# M_F_ext_breadboard.net
KiCad netlist of a schematic drawn in EAGLE
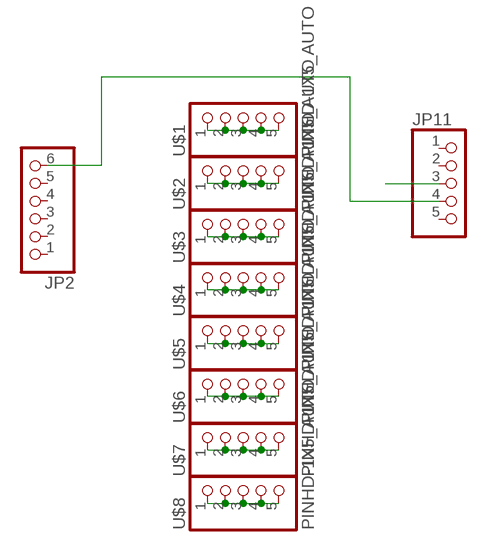
[diagram p0: schematic, sheet 1]

(export (version "E")
  (design (tool "Eeschema 10.0.6"))
  (components
    (comp (ref "JP2")
      (value "PINHD-1X6")
      (footprint "eagle-import:1X06")
      (libsource (lib "eagle-import") (part "PINHD-1X6"))
    )
    (comp (ref "JP11")
      (value "PINHD-1X5")
      (footprint "eagle-import:1X05")
      (libsource (lib "eagle-import") (part "PINHD-1X5"))
    )
    (comp (ref "U$1")
      (value "PINHD-1X5_AUTO")
      (footprint "eagle-import:1X5_AUTO")
      (libsource (lib "eagle-import") (part "PINHD-1X5_AUTO"))
    )
    (comp (ref "U$2")
      (value "PINHD-1X5_AUTO")
      (footprint "eagle-import:1X5_AUTO")
      (libsource (lib "eagle-import") (part "PINHD-1X5_AUTO"))
    )
    (comp (ref "U$3")
      (value "PINHD-1X5_AUTO")
      (footprint "eagle-import:1X5_AUTO")
      (libsource (lib "eagle-import") (part "PINHD-1X5_AUTO"))
    )
    (comp (ref "U$4")
      (value "PINHD-1X5_AUTO")
      (footprint "eagle-import:1X5_AUTO")
      (libsource (lib "eagle-import") (part "PINHD-1X5_AUTO"))
    )
    (comp (ref "U$5")
      (value "PINHD-1X5_AUTO")
      (footprint "eagle-import:1X5_AUTO")
      (libsource (lib "eagle-import") (part "PINHD-1X5_AUTO"))
    )
    (comp (ref "U$6")
      (value "PINHD-1X5_AUTO")
      (footprint "eagle-import:1X5_AUTO")
      (libsource (lib "eagle-import") (part "PINHD-1X5_AUTO"))
    )
    (comp (ref "U$7")
      (value "PINHD-1X5_AUTO")
      (footprint "eagle-import:1X5_AUTO")
      (libsource (lib "eagle-import") (part "PINHD-1X5_AUTO"))
    )
    (comp (ref "U$8")
      (value "PINHD-1X5_AUTO")
      (footprint "eagle-import:1X5_AUTO")
      (libsource (lib "eagle-import") (part "PINHD-1X5_AUTO"))
    )
  )
  (nets
    (net (code "1") (name "Net-(JP11-Pad4)") (class "Default")
      (node (ref "JP11") (pin "4") (pinfunction "4_4") (pintype "passive"))
      (node (ref "JP2") (pin "6") (pinfunction "6_6") (pintype "passive"))
    )
    (net (code "2") (name "Net-(U$1-Pad1)") (class "Default")
      (node (ref "U$1") (pin "1") (pinfunction "1_1") (pintype "passive"))
      (node (ref "U$1") (pin "2") (pinfunction "2_2") (pintype "passive"))
      (node (ref "U$1") (pin "3") (pinfunction "3_3") (pintype "passive"))
      (node (ref "U$1") (pin "4") (pinfunction "4_4") (pintype "passive"))
      (node (ref "U$1") (pin "5") (pinfunction "5_5") (pintype "passive"))
    )
    (net (code "3") (name "Net-(U$2-Pad1)") (class "Default")
      (node (ref "U$2") (pin "1") (pinfunction "1_1") (pintype "passive"))
      (node (ref "U$2") (pin "2") (pinfunction "2_2") (pintype "passive"))
      (node (ref "U$2") (pin "3") (pinfunction "3_3") (pintype "passive"))
      (node (ref "U$2") (pin "4") (pinfunction "4_4") (pintype "passive"))
      (node (ref "U$2") (pin "5") (pinfunction "5_5") (pintype "passive"))
    )
    (net (code "4") (name "Net-(U$3-Pad1)") (class "Default")
      (node (ref "U$3") (pin "1") (pinfunction "1_1") (pintype "passive"))
      (node (ref "U$3") (pin "2") (pinfunction "2_2") (pintype "passive"))
      (node (ref "U$3") (pin "3") (pinfunction "3_3") (pintype "passive"))
      (node (ref "U$3") (pin "4") (pinfunction "4_4") (pintype "passive"))
      (node (ref "U$3") (pin "5") (pinfunction "5_5") (pintype "passive"))
    )
    (net (code "5") (name "Net-(U$4-Pad1)") (class "Default")
      (node (ref "U$4") (pin "1") (pinfunction "1_1") (pintype "passive"))
      (node (ref "U$4") (pin "2") (pinfunction "2_2") (pintype "passive"))
      (node (ref "U$4") (pin "3") (pinfunction "3_3") (pintype "passive"))
      (node (ref "U$4") (pin "4") (pinfunction "4_4") (pintype "passive"))
      (node (ref "U$4") (pin "5") (pinfunction "5_5") (pintype "passive"))
    )
    (net (code "6") (name "Net-(U$5-Pad1)") (class "Default")
      (node (ref "U$5") (pin "1") (pinfunction "1_1") (pintype "passive"))
      (node (ref "U$5") (pin "2") (pinfunction "2_2") (pintype "passive"))
      (node (ref "U$5") (pin "3") (pinfunction "3_3") (pintype "passive"))
      (node (ref "U$5") (pin "4") (pinfunction "4_4") (pintype "passive"))
      (node (ref "U$5") (pin "5") (pinfunction "5_5") (pintype "passive"))
    )
    (net (code "7") (name "Net-(U$6-Pad1)") (class "Default")
      (node (ref "U$6") (pin "1") (pinfunction "1_1") (pintype "passive"))
      (node (ref "U$6") (pin "2") (pinfunction "2_2") (pintype "passive"))
      (node (ref "U$6") (pin "3") (pinfunction "3_3") (pintype "passive"))
      (node (ref "U$6") (pin "4") (pinfunction "4_4") (pintype "passive"))
      (node (ref "U$6") (pin "5") (pinfunction "5_5") (pintype "passive"))
    )
    (net (code "8") (name "Net-(U$7-Pad1)") (class "Default")
      (node (ref "U$7") (pin "1") (pinfunction "1_1") (pintype "passive"))
      (node (ref "U$7") (pin "2") (pinfunction "2_2") (pintype "passive"))
      (node (ref "U$7") (pin "3") (pinfunction "3_3") (pintype "passive"))
      (node (ref "U$7") (pin "4") (pinfunction "4_4") (pintype "passive"))
      (node (ref "U$7") (pin "5") (pinfunction "5_5") (pintype "passive"))
    )
    (net (code "9") (name "Net-(U$8-Pad1)") (class "Default")
      (node (ref "U$8") (pin "1") (pinfunction "1_1") (pintype "passive"))
      (node (ref "U$8") (pin "2") (pinfunction "2_2") (pintype "passive"))
      (node (ref "U$8") (pin "3") (pinfunction "3_3") (pintype "passive"))
      (node (ref "U$8") (pin "4") (pinfunction "4_4") (pintype "passive"))
      (node (ref "U$8") (pin "5") (pinfunction "5_5") (pintype "passive"))
    )
    (net (code "10") (name "unconnected-(JP2-Pad1)") (class "Default")
      (node (ref "JP2") (pin "1") (pinfunction "1_1") (pintype "passive"))
    )
    (net (code "11") (name "unconnected-(JP2-Pad2)") (class "Default")
      (node (ref "JP2") (pin "2") (pinfunction "2_2") (pintype "passive"))
    )
    (net (code "12") (name "unconnected-(JP2-Pad3)") (class "Default")
      (node (ref "JP2") (pin "3") (pinfunction "3_3") (pintype "passive"))
    )
    (net (code "13") (name "unconnected-(JP2-Pad4)") (class "Default")
      (node (ref "JP2") (pin "4") (pinfunction "4_4") (pintype "passive"))
    )
    (net (code "14") (name "unconnected-(JP2-Pad5)") (class "Default")
      (node (ref "JP2") (pin "5") (pinfunction "5_5") (pintype "passive"))
    )
    (net (code "15") (name "unconnected-(JP11-Pad1)") (class "Default")
      (node (ref "JP11") (pin "1") (pinfunction "1_1") (pintype "passive"))
    )
    (net (code "16") (name "unconnected-(JP11-Pad2)") (class "Default")
      (node (ref "JP11") (pin "2") (pinfunction "2_2") (pintype "passive"))
    )
    (net (code "17") (name "unconnected-(JP11-Pad3)") (class "Default")
      (node (ref "JP11") (pin "3") (pinfunction "3_3") (pintype "passive"))
    )
    (net (code "18") (name "unconnected-(JP11-Pad5)") (class "Default")
      (node (ref "JP11") (pin "5") (pinfunction "5_5") (pintype "passive"))
    )
  )
)
